# pi-crust15.net
KiCad netlist of a schematic drawn in EAGLE
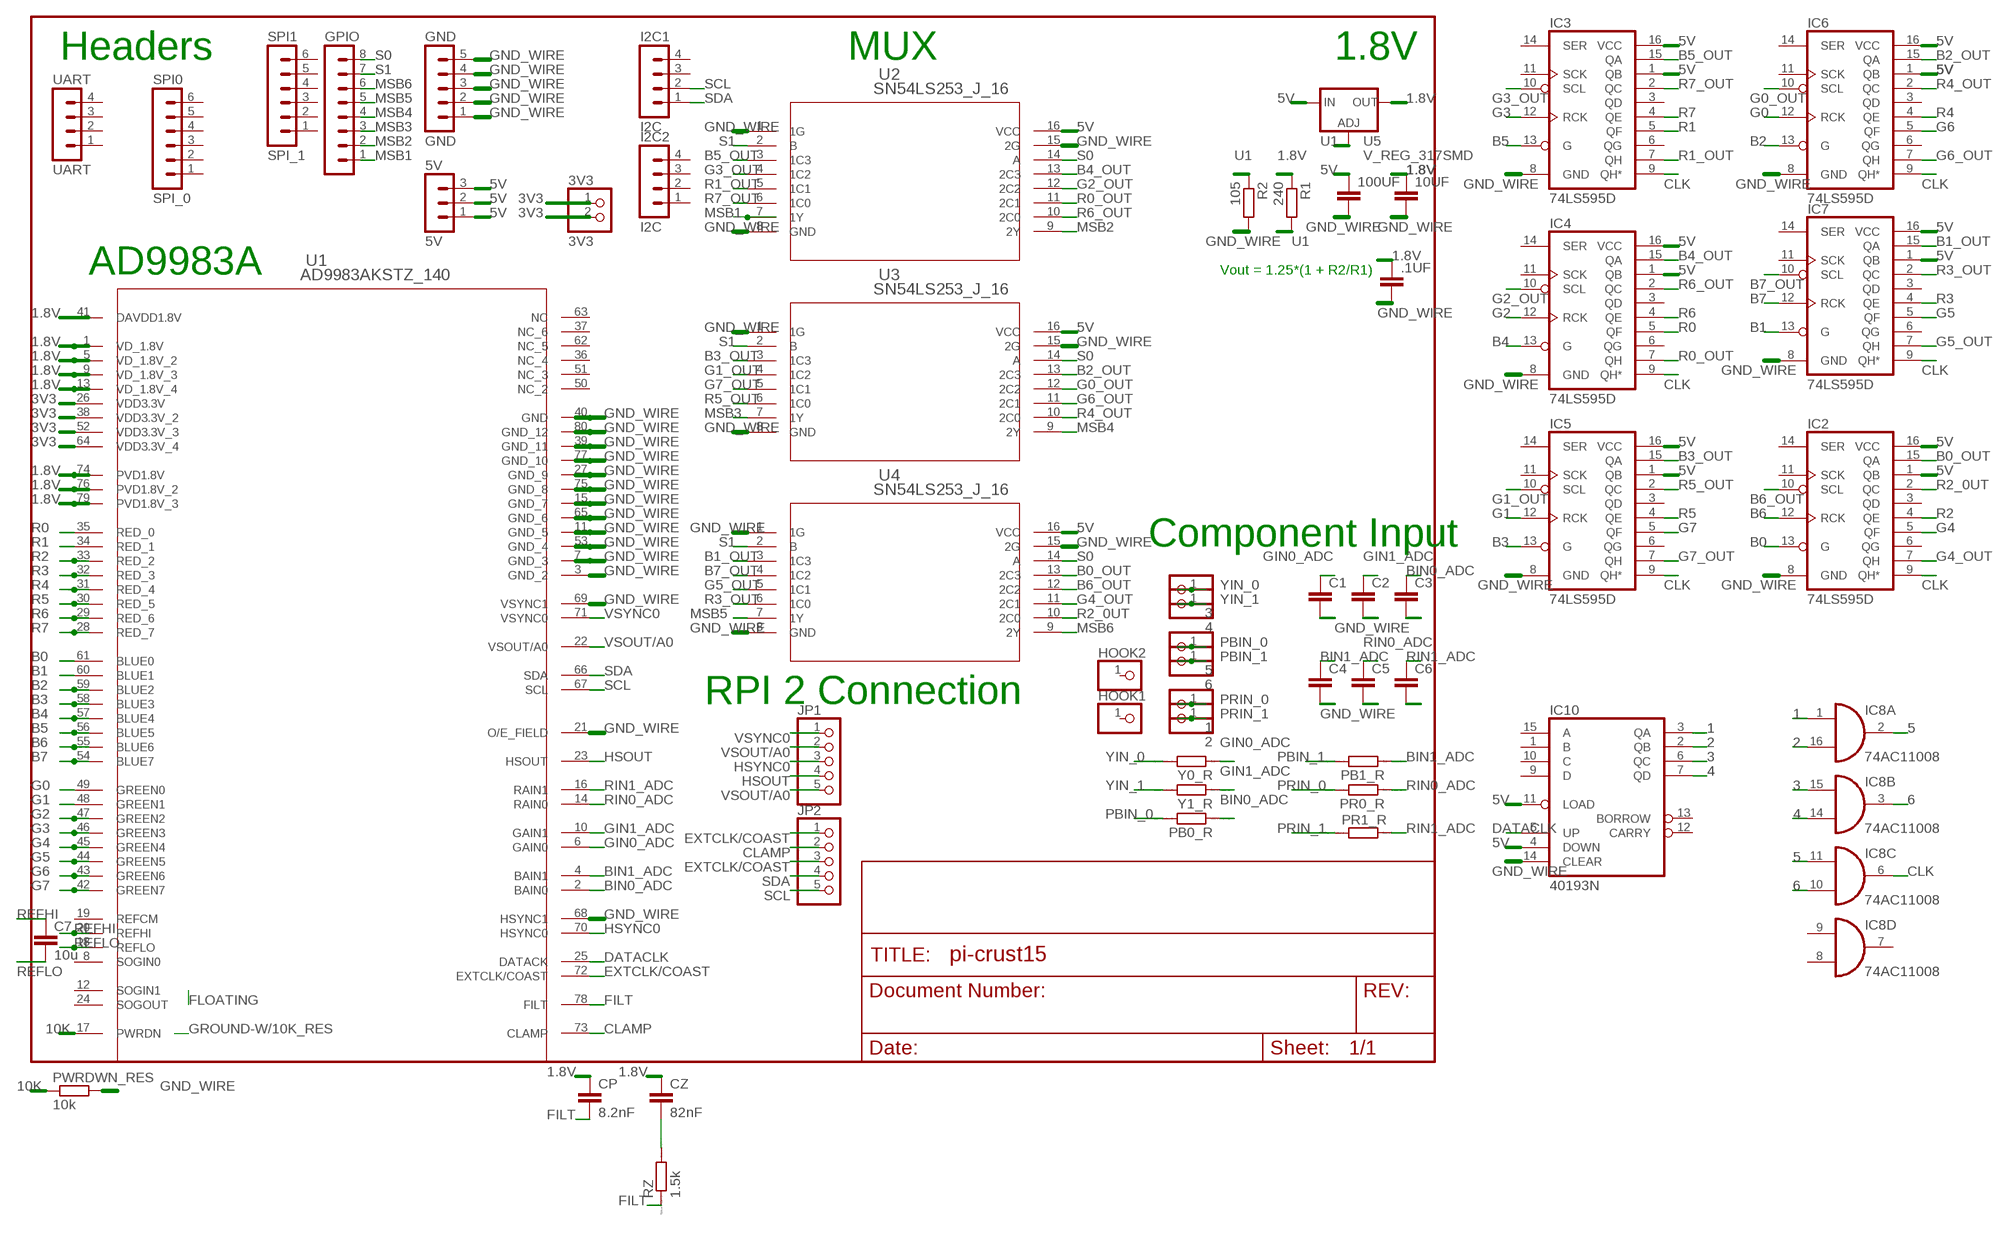
[diagram p0: schematic, sheet 1]

(export (version "E")
  (design (tool "Eeschema 10.0.6"))
  (components
    (comp (ref ".1UF")
      (value "C2.5/5")
      (footprint "eagle-import:C2.5-5")
      (libsource (lib "eagle-import") (part "C2.5/5"))
    )
    (comp (ref "1")
      (value "PINHD-1X1")
      (footprint "eagle-import:1X01")
      (libsource (lib "eagle-import") (part "PINHD-1X1"))
    )
    (comp (ref "2")
      (value "PINHD-1X1")
      (footprint "eagle-import:1X01")
      (libsource (lib "eagle-import") (part "PINHD-1X1"))
    )
    (comp (ref "3")
      (value "PINHD-1X1")
      (footprint "eagle-import:1X01")
      (libsource (lib "eagle-import") (part "PINHD-1X1"))
    )
    (comp (ref "3V3")
      (value "3V3")
      (footprint "eagle-import:1X02")
      (libsource (lib "eagle-import") (part "PINHD-1X2"))
    )
    (comp (ref "4")
      (value "PINHD-1X1")
      (footprint "eagle-import:1X01")
      (libsource (lib "eagle-import") (part "PINHD-1X1"))
    )
    (comp (ref "5")
      (value "PINHD-1X1")
      (footprint "eagle-import:1X01")
      (libsource (lib "eagle-import") (part "PINHD-1X1"))
    )
    (comp (ref "5V")
      (value "5V")
      (footprint "eagle-import:MA03-1")
      (libsource (lib "eagle-import") (part "MA03-1"))
    )
    (comp (ref "6")
      (value "PINHD-1X1")
      (footprint "eagle-import:1X01")
      (libsource (lib "eagle-import") (part "PINHD-1X1"))
    )
    (comp (ref "10UF")
      (value "C2.5/5")
      (footprint "eagle-import:C2.5-5")
      (libsource (lib "eagle-import") (part "C2.5/5"))
    )
    (comp (ref "100UF")
      (value "C2.5/5")
      (footprint "eagle-import:C2.5-5")
      (libsource (lib "eagle-import") (part "C2.5/5"))
    )
    (comp (ref "C1")
      (value "C2.5/5")
      (footprint "eagle-import:C2.5-5")
      (libsource (lib "eagle-import") (part "C2.5/5"))
    )
    (comp (ref "C2")
      (value "C2.5/5")
      (footprint "eagle-import:C2.5-5")
      (libsource (lib "eagle-import") (part "C2.5/5"))
    )
    (comp (ref "C3")
      (value "C2.5/5")
      (footprint "eagle-import:C2.5-5")
      (libsource (lib "eagle-import") (part "C2.5/5"))
    )
    (comp (ref "C4")
      (value "C2.5/5")
      (footprint "eagle-import:C2.5-5")
      (libsource (lib "eagle-import") (part "C2.5/5"))
    )
    (comp (ref "C5")
      (value "C2.5/5")
      (footprint "eagle-import:C2.5-5")
      (libsource (lib "eagle-import") (part "C2.5/5"))
    )
    (comp (ref "C6")
      (value "C2.5/5")
      (footprint "eagle-import:C2.5-5")
      (libsource (lib "eagle-import") (part "C2.5/5"))
    )
    (comp (ref "C7")
      (value "10u")
      (footprint "eagle-import:C2.5-5")
      (libsource (lib "eagle-import") (part "C2.5/5"))
    )
    (comp (ref "CP")
      (value "8.2nF")
      (footprint "eagle-import:C2.5-5")
      (libsource (lib "eagle-import") (part "C2.5/5"))
    )
    (comp (ref "CZ")
      (value "82nF")
      (footprint "eagle-import:C2.5-5")
      (libsource (lib "eagle-import") (part "C2.5/5"))
    )
    (comp (ref "GND")
      (value "GND")
      (footprint "eagle-import:MA05-1")
      (libsource (lib "eagle-import") (part "MA05-1"))
    )
    (comp (ref "GPIO")
      (value "MA08-1")
      (footprint "eagle-import:MA08-1")
      (libsource (lib "eagle-import") (part "MA08-1"))
    )
    (comp (ref "HOOK1")
      (value "PINHD-1X1")
      (footprint "eagle-import:1X01")
      (libsource (lib "eagle-import") (part "PINHD-1X1"))
    )
    (comp (ref "HOOK2")
      (value "PINHD-1X1")
      (footprint "eagle-import:1X01")
      (libsource (lib "eagle-import") (part "PINHD-1X1"))
    )
    (comp (ref "I2C1")
      (value "I2C")
      (footprint "eagle-import:MA04-1")
      (libsource (lib "eagle-import") (part "MA04-1"))
    )
    (comp (ref "I2C2")
      (value "I2C")
      (footprint "eagle-import:MA04-1")
      (libsource (lib "eagle-import") (part "MA04-1"))
    )
    (comp (ref "IC2")
      (value "74LS595D")
      (footprint "eagle-import:SO16")
      (libsource (lib "eagle-import") (part "74595DLS"))
    )
    (comp (ref "IC3")
      (value "74LS595D")
      (footprint "eagle-import:SO16")
      (libsource (lib "eagle-import") (part "74595DLS"))
    )
    (comp (ref "IC4")
      (value "74LS595D")
      (footprint "eagle-import:SO16")
      (libsource (lib "eagle-import") (part "74595DLS"))
    )
    (comp (ref "IC5")
      (value "74LS595D")
      (footprint "eagle-import:SO16")
      (libsource (lib "eagle-import") (part "74595DLS"))
    )
    (comp (ref "IC6")
      (value "74LS595D")
      (footprint "eagle-import:SO16")
      (libsource (lib "eagle-import") (part "74595DLS"))
    )
    (comp (ref "IC7")
      (value "74LS595D")
      (footprint "eagle-import:SO16")
      (libsource (lib "eagle-import") (part "74595DLS"))
    )
    (comp (ref "IC8")
      (value "74AC11008")
      (footprint "eagle-import:DIL16")
      (libsource (lib "eagle-import") (part "74AC11008"))
    )
    (comp (ref "IC10")
      (value "40193N")
      (footprint "eagle-import:DIL16")
      (libsource (lib "eagle-import") (part "40193N"))
    )
    (comp (ref "JP1")
      (value "PINHD-1X5")
      (footprint "eagle-import:1X05")
      (libsource (lib "eagle-import") (part "PINHD-1X5"))
    )
    (comp (ref "JP2")
      (value "PINHD-1X5")
      (footprint "eagle-import:1X05")
      (libsource (lib "eagle-import") (part "PINHD-1X5"))
    )
    (comp (ref "PB0_R")
      (value "R0204/7")
      (footprint "eagle-import:0204_7")
      (libsource (lib "eagle-import") (part "R0204/7"))
    )
    (comp (ref "PB1_R")
      (value "R0204/7")
      (footprint "eagle-import:0204_7")
      (libsource (lib "eagle-import") (part "R0204/7"))
    )
    (comp (ref "PR0_R")
      (value "R0204/7")
      (footprint "eagle-import:0204_7")
      (libsource (lib "eagle-import") (part "R0204/7"))
    )
    (comp (ref "PR1_R")
      (value "R0204/7")
      (footprint "eagle-import:0204_7")
      (libsource (lib "eagle-import") (part "R0204/7"))
    )
    (comp (ref "PWRDWN_RES")
      (value "10k")
      (footprint "eagle-import:0204_7")
      (libsource (lib "eagle-import") (part "R-EU_0204/7"))
    )
    (comp (ref "R1")
      (value "240")
      (footprint "eagle-import:0204_7")
      (libsource (lib "eagle-import") (part "R-EU_0204/7"))
    )
    (comp (ref "R2")
      (value "105")
      (footprint "eagle-import:0204_7")
      (libsource (lib "eagle-import") (part "R-EU_0204/7"))
    )
    (comp (ref "RZ")
      (value "1.5k")
      (footprint "eagle-import:0204_7")
      (libsource (lib "eagle-import") (part "R0204/7"))
    )
    (comp (ref "SPI0")
      (value "SPI_0")
      (footprint "eagle-import:MA06-1")
      (libsource (lib "eagle-import") (part "MA06-1"))
    )
    (comp (ref "SPI1")
      (value "SPI_1")
      (footprint "eagle-import:MA06-1")
      (libsource (lib "eagle-import") (part "MA06-1"))
    )
    (comp (ref "U1")
      (value "AD9983AKSTZ_140")
      (footprint "eagle-import:ST_80_2")
      (libsource (lib "eagle-import") (part "AD9983AKSTZ_140"))
    )
    (comp (ref "U2")
      (value "SN54LS253_J_16")
      (footprint "eagle-import:J16")
      (fields
        (field (name "GENERIC_PART_NUMBER") "SN54LS253")
        (field (name "MANUFACTURER") "Texas Instruments")
      )
      (libsource (lib "eagle-import") (part "SN54LS253_J_16"))
    )
    (comp (ref "U3")
      (value "SN54LS253_J_16")
      (footprint "eagle-import:J16")
      (fields
        (field (name "GENERIC_PART_NUMBER") "SN54LS253")
        (field (name "MANUFACTURER") "Texas Instruments")
      )
      (libsource (lib "eagle-import") (part "SN54LS253_J_16"))
    )
    (comp (ref "U4")
      (value "SN54LS253_J_16")
      (footprint "eagle-import:J16")
      (fields
        (field (name "GENERIC_PART_NUMBER") "SN54LS253")
        (field (name "MANUFACTURER") "Texas Instruments")
      )
      (libsource (lib "eagle-import") (part "SN54LS253_J_16"))
    )
    (comp (ref "U5")
      (value "V_REG_317SMD")
      (footprint "eagle-import:SOT223")
      (libsource (lib "eagle-import") (part "V_REG_317SMD"))
    )
    (comp (ref "UART")
      (value "UART")
      (footprint "eagle-import:MA04-1")
      (libsource (lib "eagle-import") (part "MA04-1"))
    )
    (comp (ref "Y0_R")
      (value "R0204/7")
      (footprint "eagle-import:0204_7")
      (libsource (lib "eagle-import") (part "R0204/7"))
    )
    (comp (ref "Y1_R")
      (value "R0204/7")
      (footprint "eagle-import:0204_7")
      (libsource (lib "eagle-import") (part "R0204/7"))
    )
  )
  (nets
    (net (code "1") (name "/1") (class "Default")
      (node (ref "IC10") (pin "3") (pinfunction "QA_3") (pintype "output"))
      (node (ref "IC8") (pin "1") (pinfunction "I0_1") (pintype "input"))
    )
    (net (code "2") (name "/1.8V") (class "Default")
      (node (ref ".1UF") (pin "1") (pinfunction "1_1") (pintype "passive"))
      (node (ref "10UF") (pin "1") (pinfunction "1_1") (pintype "passive"))
      (node (ref "CP") (pin "1") (pinfunction "1_1") (pintype "passive"))
      (node (ref "CZ") (pin "1") (pinfunction "1_1") (pintype "passive"))
      (node (ref "R1") (pin "1") (pinfunction "1_1") (pintype "passive"))
      (node (ref "U1") (pin "1") (pinfunction "VD_1.8V_1") (pintype "passive"))
      (node (ref "U1") (pin "13") (pinfunction "VD_1.8V_4_13") (pintype "passive"))
      (node (ref "U1") (pin "41") (pinfunction "DAVDD1.8V_41") (pintype "passive"))
      (node (ref "U1") (pin "5") (pinfunction "VD_1.8V_2_5") (pintype "passive"))
      (node (ref "U1") (pin "74") (pinfunction "PVD1.8V_74") (pintype "passive"))
      (node (ref "U1") (pin "76") (pinfunction "PVD1.8V_2_76") (pintype "passive"))
      (node (ref "U1") (pin "79") (pinfunction "PVD1.8V_3_79") (pintype "passive"))
      (node (ref "U1") (pin "9") (pinfunction "VD_1.8V_3_9") (pintype "passive"))
      (node (ref "U5") (pin "2") (pinfunction "OUT_2") (pintype "output"))
    )
    (net (code "3") (name "/2") (class "Default")
      (node (ref "IC10") (pin "2") (pinfunction "QB_2") (pintype "output"))
      (node (ref "IC8") (pin "16") (pinfunction "I1_16") (pintype "input"))
    )
    (net (code "4") (name "/3") (class "Default")
      (node (ref "IC10") (pin "6") (pinfunction "QC_6") (pintype "output"))
      (node (ref "IC8") (pin "15") (pinfunction "I0_15") (pintype "input"))
    )
    (net (code "5") (name "/3V3") (class "Default")
      (node (ref "3V3") (pin "1") (pinfunction "1_1") (pintype "passive"))
      (node (ref "3V3") (pin "2") (pinfunction "2_2") (pintype "passive"))
      (node (ref "U1") (pin "26") (pinfunction "VDD3.3V_26") (pintype "passive"))
      (node (ref "U1") (pin "38") (pinfunction "VDD3.3V_2_38") (pintype "passive"))
      (node (ref "U1") (pin "52") (pinfunction "VDD3.3V_3_52") (pintype "passive"))
      (node (ref "U1") (pin "64") (pinfunction "VDD3.3V_4_64") (pintype "passive"))
    )
    (net (code "6") (name "/4") (class "Default")
      (node (ref "IC10") (pin "7") (pinfunction "QD_7") (pintype "output"))
      (node (ref "IC8") (pin "14") (pinfunction "I1_14") (pintype "input"))
    )
    (net (code "7") (name "/5") (class "Default")
      (node (ref "IC8") (pin "11") (pinfunction "I0_11") (pintype "input"))
      (node (ref "IC8") (pin "2") (pinfunction "O_2") (pintype "output"))
    )
    (net (code "8") (name "/5V") (class "Default")
      (node (ref "100UF") (pin "1") (pinfunction "1_1") (pintype "passive"))
      (node (ref "5V") (pin "1") (pinfunction "1_1") (pintype "passive"))
      (node (ref "5V") (pin "2") (pinfunction "2_2") (pintype "passive"))
      (node (ref "5V") (pin "3") (pinfunction "3_3") (pintype "passive"))
      (node (ref "IC10") (pin "11") (pinfunction "LOAD_11") (pintype "input"))
      (node (ref "IC10") (pin "4") (pinfunction "DOWN_4") (pintype "input"))
      (node (ref "IC2") (pin "1") (pinfunction "QB_1") (pintype "tri_state"))
      (node (ref "IC2") (pin "16") (pinfunction "VCC_16") (pintype "power_in"))
      (node (ref "IC3") (pin "1") (pinfunction "QB_1") (pintype "tri_state"))
      (node (ref "IC3") (pin "16") (pinfunction "VCC_16") (pintype "power_in"))
      (node (ref "IC4") (pin "1") (pinfunction "QB_1") (pintype "tri_state"))
      (node (ref "IC4") (pin "16") (pinfunction "VCC_16") (pintype "power_in"))
      (node (ref "IC5") (pin "1") (pinfunction "QB_1") (pintype "tri_state"))
      (node (ref "IC5") (pin "16") (pinfunction "VCC_16") (pintype "power_in"))
      (node (ref "IC6") (pin "1") (pinfunction "QB_1") (pintype "tri_state"))
      (node (ref "IC6") (pin "16") (pinfunction "VCC_16") (pintype "power_in"))
      (node (ref "IC7") (pin "1") (pinfunction "QB_1") (pintype "tri_state"))
      (node (ref "IC7") (pin "16") (pinfunction "VCC_16") (pintype "power_in"))
      (node (ref "U2") (pin "16") (pinfunction "VCC_16") (pintype "power_in"))
      (node (ref "U3") (pin "16") (pinfunction "VCC_16") (pintype "power_in"))
      (node (ref "U4") (pin "16") (pinfunction "VCC_16") (pintype "power_in"))
      (node (ref "U5") (pin "3") (pinfunction "IN_3") (pintype "input"))
    )
    (net (code "9") (name "/6") (class "Default")
      (node (ref "IC8") (pin "10") (pinfunction "I1_10") (pintype "input"))
      (node (ref "IC8") (pin "3") (pinfunction "O_3") (pintype "output"))
    )
    (net (code "10") (name "/10K") (class "Default")
      (node (ref "PWRDWN_RES") (pin "1") (pinfunction "1_1") (pintype "passive"))
      (node (ref "U1") (pin "17") (pinfunction "PWRDN_17") (pintype "passive"))
    )
    (net (code "11") (name "/B0") (class "Default")
      (node (ref "IC2") (pin "13") (pinfunction "G_13") (pintype "input"))
      (node (ref "U1") (pin "61") (pinfunction "BLUE0_61") (pintype "passive"))
    )
    (net (code "12") (name "/B0_OUT") (class "Default")
      (node (ref "IC2") (pin "15") (pinfunction "QA_15") (pintype "tri_state"))
      (node (ref "U4") (pin "13") (pinfunction "2C3_13") (pintype "input"))
    )
    (net (code "13") (name "/B1") (class "Default")
      (node (ref "IC7") (pin "13") (pinfunction "G_13") (pintype "input"))
      (node (ref "U1") (pin "60") (pinfunction "BLUE1_60") (pintype "passive"))
    )
    (net (code "14") (name "/B1_OUT") (class "Default")
      (node (ref "IC7") (pin "15") (pinfunction "QA_15") (pintype "tri_state"))
      (node (ref "U4") (pin "3") (pinfunction "1C3_3") (pintype "input"))
    )
    (net (code "15") (name "/B2") (class "Default")
      (node (ref "IC6") (pin "13") (pinfunction "G_13") (pintype "input"))
      (node (ref "U1") (pin "59") (pinfunction "BLUE2_59") (pintype "passive"))
    )
    (net (code "16") (name "/B2_OUT") (class "Default")
      (node (ref "IC6") (pin "15") (pinfunction "QA_15") (pintype "tri_state"))
      (node (ref "U3") (pin "13") (pinfunction "2C3_13") (pintype "input"))
    )
    (net (code "17") (name "/B3") (class "Default")
      (node (ref "IC5") (pin "13") (pinfunction "G_13") (pintype "input"))
      (node (ref "U1") (pin "58") (pinfunction "BLUE3_58") (pintype "passive"))
    )
    (net (code "18") (name "/B3_OUT") (class "Default")
      (node (ref "IC5") (pin "15") (pinfunction "QA_15") (pintype "tri_state"))
      (node (ref "U3") (pin "3") (pinfunction "1C3_3") (pintype "input"))
    )
    (net (code "19") (name "/B4") (class "Default")
      (node (ref "IC4") (pin "13") (pinfunction "G_13") (pintype "input"))
      (node (ref "U1") (pin "57") (pinfunction "BLUE4_57") (pintype "passive"))
    )
    (net (code "20") (name "/B4_OUT") (class "Default")
      (node (ref "IC4") (pin "15") (pinfunction "QA_15") (pintype "tri_state"))
      (node (ref "U2") (pin "13") (pinfunction "2C3_13") (pintype "input"))
    )
    (net (code "21") (name "/B5") (class "Default")
      (node (ref "IC3") (pin "13") (pinfunction "G_13") (pintype "input"))
      (node (ref "U1") (pin "56") (pinfunction "BLUE5_56") (pintype "passive"))
    )
    (net (code "22") (name "/B5_OUT") (class "Default")
      (node (ref "IC3") (pin "15") (pinfunction "QA_15") (pintype "tri_state"))
      (node (ref "U2") (pin "3") (pinfunction "1C3_3") (pintype "input"))
    )
    (net (code "23") (name "/B6") (class "Default")
      (node (ref "IC2") (pin "12") (pinfunction "RCK_12") (pintype "input"))
      (node (ref "U1") (pin "55") (pinfunction "BLUE6_55") (pintype "passive"))
    )
    (net (code "24") (name "/B6_OUT") (class "Default")
      (node (ref "IC2") (pin "10") (pinfunction "SCL_10") (pintype "input"))
      (node (ref "U4") (pin "12") (pinfunction "2C2_12") (pintype "input"))
    )
    (net (code "25") (name "/B7") (class "Default")
      (node (ref "IC7") (pin "12") (pinfunction "RCK_12") (pintype "input"))
      (node (ref "U1") (pin "54") (pinfunction "BLUE7_54") (pintype "passive"))
    )
    (net (code "26") (name "/B7_OUT") (class "Default")
      (node (ref "IC7") (pin "10") (pinfunction "SCL_10") (pintype "input"))
      (node (ref "U4") (pin "4") (pinfunction "1C2_4") (pintype "input"))
    )
    (net (code "27") (name "/BIN0_ADC") (class "Default")
      (node (ref "C3") (pin "1") (pinfunction "1_1") (pintype "passive"))
      (node (ref "PB0_R") (pin "1") (pinfunction "1_1") (pintype "passive"))
      (node (ref "U1") (pin "2") (pinfunction "BAIN0_2") (pintype "passive"))
    )
    (net (code "28") (name "/BIN1_ADC") (class "Default")
      (node (ref "C4") (pin "1") (pinfunction "1_1") (pintype "passive"))
      (node (ref "PB1_R") (pin "1") (pinfunction "1_1") (pintype "passive"))
      (node (ref "U1") (pin "4") (pinfunction "BAIN1_4") (pintype "passive"))
    )
    (net (code "29") (name "/CLAMP") (class "Default")
      (node (ref "JP2") (pin "2") (pinfunction "2_2") (pintype "passive"))
      (node (ref "U1") (pin "73") (pinfunction "CLAMP_73") (pintype "passive"))
    )
    (net (code "30") (name "/CLK") (class "Default")
      (node (ref "IC2") (pin "9") (pinfunction "QH*_9") (pintype "tri_state"))
      (node (ref "IC3") (pin "9") (pinfunction "QH*_9") (pintype "tri_state"))
      (node (ref "IC4") (pin "9") (pinfunction "QH*_9") (pintype "tri_state"))
      (node (ref "IC5") (pin "9") (pinfunction "QH*_9") (pintype "tri_state"))
      (node (ref "IC6") (pin "9") (pinfunction "QH*_9") (pintype "tri_state"))
      (node (ref "IC7") (pin "9") (pinfunction "QH*_9") (pintype "tri_state"))
      (node (ref "IC8") (pin "6") (pinfunction "O_6") (pintype "output"))
    )
    (net (code "31") (name "/DATACLK") (class "Default")
      (node (ref "IC10") (pin "5") (pinfunction "UP_5") (pintype "input"))
      (node (ref "U1") (pin "25") (pinfunction "DATACK_25") (pintype "passive"))
    )
    (net (code "32") (name "/EXTCLK{slash}COAST") (class "Default")
      (node (ref "JP2") (pin "1") (pinfunction "1_1") (pintype "passive"))
      (node (ref "JP2") (pin "3") (pinfunction "3_3") (pintype "passive"))
      (node (ref "U1") (pin "72") (pinfunction "EXTCLK/COAST_72") (pintype "passive"))
    )
    (net (code "33") (name "/FILT") (class "Default")
      (node (ref "CP") (pin "2") (pinfunction "2_2") (pintype "passive"))
      (node (ref "RZ") (pin "1") (pinfunction "1_1") (pintype "passive"))
      (node (ref "U1") (pin "78") (pinfunction "FILT_78") (pintype "passive"))
    )
    (net (code "35") (name "/G0") (class "Default")
      (node (ref "IC6") (pin "12") (pinfunction "RCK_12") (pintype "input"))
      (node (ref "U1") (pin "49") (pinfunction "GREEN0_49") (pintype "passive"))
    )
    (net (code "36") (name "/G0_OUT") (class "Default")
      (node (ref "IC6") (pin "10") (pinfunction "SCL_10") (pintype "input"))
      (node (ref "U3") (pin "12") (pinfunction "2C2_12") (pintype "input"))
    )
    (net (code "37") (name "/G1") (class "Default")
      (node (ref "IC5") (pin "12") (pinfunction "RCK_12") (pintype "input"))
      (node (ref "U1") (pin "48") (pinfunction "GREEN1_48") (pintype "passive"))
    )
    (net (code "38") (name "/G1_OUT") (class "Default")
      (node (ref "IC5") (pin "10") (pinfunction "SCL_10") (pintype "input"))
      (node (ref "U3") (pin "4") (pinfunction "1C2_4") (pintype "input"))
    )
    (net (code "39") (name "/G2") (class "Default")
      (node (ref "IC4") (pin "12") (pinfunction "RCK_12") (pintype "input"))
      (node (ref "U1") (pin "47") (pinfunction "GREEN2_47") (pintype "passive"))
    )
    (net (code "40") (name "/G2_OUT") (class "Default")
      (node (ref "IC4") (pin "10") (pinfunction "SCL_10") (pintype "input"))
      (node (ref "U2") (pin "12") (pinfunction "2C2_12") (pintype "input"))
    )
    (net (code "41") (name "/G3") (class "Default")
      (node (ref "IC3") (pin "12") (pinfunction "RCK_12") (pintype "input"))
      (node (ref "U1") (pin "46") (pinfunction "GREEN3_46") (pintype "passive"))
    )
    (net (code "42") (name "/G3_OUT") (class "Default")
      (node (ref "IC3") (pin "10") (pinfunction "SCL_10") (pintype "input"))
      (node (ref "U2") (pin "4") (pinfunction "1C2_4") (pintype "input"))
    )
    (net (code "43") (name "/G4") (class "Default")
      (node (ref "IC2") (pin "5") (pinfunction "QF_5") (pintype "tri_state"))
      (node (ref "U1") (pin "45") (pinfunction "GREEN4_45") (pintype "passive"))
    )
    (net (code "44") (name "/G4_OUT") (class "Default")
      (node (ref "IC2") (pin "7") (pinfunction "QH_7") (pintype "tri_state"))
      (node (ref "U4") (pin "11") (pinfunction "2C1_11") (pintype "input"))
    )
    (net (code "45") (name "/G5") (class "Default")
      (node (ref "IC7") (pin "5") (pinfunction "QF_5") (pintype "tri_state"))
      (node (ref "U1") (pin "44") (pinfunction "GREEN5_44") (pintype "passive"))
    )
    (net (code "46") (name "/G5_OUT") (class "Default")
      (node (ref "IC7") (pin "7") (pinfunction "QH_7") (pintype "tri_state"))
      (node (ref "U4") (pin "5") (pinfunction "1C1_5") (pintype "input"))
    )
    (net (code "47") (name "/G6") (class "Default")
      (node (ref "IC6") (pin "5") (pinfunction "QF_5") (pintype "tri_state"))
      (node (ref "U1") (pin "43") (pinfunction "GREEN6_43") (pintype "passive"))
    )
    (net (code "48") (name "/G6_OUT") (class "Default")
      (node (ref "IC6") (pin "7") (pinfunction "QH_7") (pintype "tri_state"))
      (node (ref "U3") (pin "11") (pinfunction "2C1_11") (pintype "input"))
    )
    (net (code "49") (name "/G7") (class "Default")
      (node (ref "IC5") (pin "5") (pinfunction "QF_5") (pintype "tri_state"))
      (node (ref "U1") (pin "42") (pinfunction "GREEN7_42") (pintype "passive"))
    )
    (net (code "50") (name "/G7_OUT") (class "Default")
      (node (ref "IC5") (pin "7") (pinfunction "QH_7") (pintype "tri_state"))
      (node (ref "U3") (pin "5") (pinfunction "1C1_5") (pintype "input"))
    )
    (net (code "51") (name "/GIN0_ADC") (class "Default")
      (node (ref "C1") (pin "1") (pinfunction "1_1") (pintype "passive"))
      (node (ref "U1") (pin "6") (pinfunction "GAIN0_6") (pintype "passive"))
      (node (ref "Y0_R") (pin "1") (pinfunction "1_1") (pintype "passive"))
    )
    (net (code "52") (name "/GIN1_ADC") (class "Default")
      (node (ref "C2") (pin "1") (pinfunction "1_1") (pintype "passive"))
      (node (ref "U1") (pin "10") (pinfunction "GAIN1_10") (pintype "passive"))
      (node (ref "Y1_R") (pin "1") (pinfunction "1_1") (pintype "passive"))
    )
    (net (code "53") (name "/GND_WIRE") (class "Default")
      (node (ref ".1UF") (pin "2") (pinfunction "2_2") (pintype "passive"))
      (node (ref "100UF") (pin "2") (pinfunction "2_2") (pintype "passive"))
      (node (ref "10UF") (pin "2") (pinfunction "2_2") (pintype "passive"))
      (node (ref "C1") (pin "2") (pinfunction "2_2") (pintype "passive"))
      (node (ref "C2") (pin "2") (pinfunction "2_2") (pintype "passive"))
      (node (ref "C3") (pin "2") (pinfunction "2_2") (pintype "passive"))
      (node (ref "C4") (pin "2") (pinfunction "2_2") (pintype "passive"))
      (node (ref "C5") (pin "2") (pinfunction "2_2") (pintype "passive"))
      (node (ref "C6") (pin "2") (pinfunction "2_2") (pintype "passive"))
      (node (ref "GND") (pin "1") (pinfunction "1_1") (pintype "passive"))
      (node (ref "GND") (pin "2") (pinfunction "2_2") (pintype "passive"))
      (node (ref "GND") (pin "3") (pinfunction "3_3") (pintype "passive"))
      (node (ref "GND") (pin "4") (pinfunction "4_4") (pintype "passive"))
      (node (ref "GND") (pin "5") (pinfunction "5_5") (pintype "passive"))
      (node (ref "IC10") (pin "14") (pinfunction "CLEAR_14") (pintype "input"))
      (node (ref "IC2") (pin "8") (pinfunction "GND_8") (pintype "power_in"))
      (node (ref "IC3") (pin "8") (pinfunction "GND_8") (pintype "power_in"))
      (node (ref "IC4") (pin "8") (pinfunction "GND_8") (pintype "power_in"))
      (node (ref "IC5") (pin "8") (pinfunction "GND_8") (pintype "power_in"))
      (node (ref "IC6") (pin "8") (pinfunction "GND_8") (pintype "power_in"))
      (node (ref "IC7") (pin "8") (pinfunction "GND_8") (pintype "power_in"))
      (node (ref "PWRDWN_RES") (pin "2") (pinfunction "2_2") (pintype "passive"))
      (node (ref "R2") (pin "2") (pinfunction "2_2") (pintype "passive"))
      (node (ref "U1") (pin "11") (pinfunction "GND_5_11") (pintype "passive"))
      (node (ref "U1") (pin "15") (pinfunction "GND_7_15") (pintype "passive"))
      (node (ref "U1") (pin "21") (pinfunction "O/E_FIELD_21") (pintype "passive"))
      (node (ref "U1") (pin "27") (pinfunction "GND_9_27") (pintype "passive"))
      (node (ref "U1") (pin "3") (pinfunction "GND_2_3") (pintype "passive"))
      (node (ref "U1") (pin "39") (pinfunction "GND_11_39") (pintype "passive"))
      (node (ref "U1") (pin "40") (pinfunction "GND_40") (pintype "passive"))
      (node (ref "U1") (pin "53") (pinfunction "GND_4_53") (pintype "passive"))
      (node (ref "U1") (pin "65") (pinfunction "GND_6_65") (pintype "passive"))
      (node (ref "U1") (pin "68") (pinfunction "HSYNC1_68") (pintype "passive"))
      (node (ref "U1") (pin "69") (pinfunction "VSYNC1_69") (pintype "passive"))
      (node (ref "U1") (pin "7") (pinfunction "GND_3_7") (pintype "passive"))
      (node (ref "U1") (pin "75") (pinfunction "GND_8_75") (pintype "passive"))
      (node (ref "U1") (pin "77") (pinfunction "GND_10_77") (pintype "passive"))
      (node (ref "U1") (pin "80") (pinfunction "GND_12_80") (pintype "passive"))
      (node (ref "U2") (pin "1") (pinfunction "1G_1") (pintype "input"))
      (node (ref "U2") (pin "15") (pinfunction "2G_15") (pintype "input"))
      (node (ref "U2") (pin "8") (pinfunction "GND_8") (pintype "power_in"))
      (node (ref "U3") (pin "1") (pinfunction "1G_1") (pintype "input"))
      (node (ref "U3") (pin "15") (pinfunction "2G_15") (pintype "input"))
      (node (ref "U3") (pin "8") (pinfunction "GND_8") (pintype "power_in"))
      (node (ref "U4") (pin "1") (pinfunction "1G_1") (pintype "input"))
      (node (ref "U4") (pin "15") (pinfunction "2G_15") (pintype "input"))
      (node (ref "U4") (pin "8") (pinfunction "GND_8") (pintype "power_in"))
    )
    (net (code "55") (name "/HSOUT") (class "Default")
      (node (ref "JP1") (pin "4") (pinfunction "4_4") (pintype "passive"))
      (node (ref "U1") (pin "23") (pinfunction "HSOUT_23") (pintype "passive"))
    )
    (net (code "56") (name "/HSYNC0") (class "Default")
      (node (ref "JP1") (pin "3") (pinfunction "3_3") (pintype "passive"))
      (node (ref "U1") (pin "70") (pinfunction "HSYNC0_70") (pintype "passive"))
    )
    (net (code "57") (name "/MSB1") (class "Default")
      (node (ref "GPIO") (pin "1") (pinfunction "1_1") (pintype "passive"))
      (node (ref "U2") (pin "7") (pinfunction "1Y_7") (pintype "output"))
    )
    (net (code "58") (name "/MSB2") (class "Default")
      (node (ref "GPIO") (pin "2") (pinfunction "2_2") (pintype "passive"))
      (node (ref "U2") (pin "9") (pinfunction "2Y_9") (pintype "output"))
    )
    (net (code "59") (name "/MSB3") (class "Default")
      (node (ref "GPIO") (pin "3") (pinfunction "3_3") (pintype "passive"))
      (node (ref "U3") (pin "7") (pinfunction "1Y_7") (pintype "output"))
    )
    (net (code "60") (name "/MSB4") (class "Default")
      (node (ref "GPIO") (pin "4") (pinfunction "4_4") (pintype "passive"))
      (node (ref "U3") (pin "9") (pinfunction "2Y_9") (pintype "output"))
    )
    (net (code "61") (name "/MSB5") (class "Default")
      (node (ref "GPIO") (pin "5") (pinfunction "5_5") (pintype "passive"))
      (node (ref "U4") (pin "7") (pinfunction "1Y_7") (pintype "output"))
    )
    (net (code "62") (name "/MSB6") (class "Default")
      (node (ref "GPIO") (pin "6") (pinfunction "6_6") (pintype "passive"))
      (node (ref "U4") (pin "9") (pinfunction "2Y_9") (pintype "output"))
    )
    (net (code "63") (name "/PBIN_0") (class "Default")
      (node (ref "5") (pin "1") (pinfunction "1_1") (pintype "passive"))
      (node (ref "PB0_R") (pin "2") (pinfunction "2_2") (pintype "passive"))
    )
    (net (code "64") (name "/PBIN_1") (class "Default")
      (node (ref "6") (pin "1") (pinfunction "1_1") (pintype "passive"))
      (node (ref "PB1_R") (pin "2") (pinfunction "2_2") (pintype "passive"))
    )
    (net (code "65") (name "/PRIN_0") (class "Default")
      (node (ref "1") (pin "1") (pinfunction "1_1") (pintype "passive"))
      (node (ref "PR0_R") (pin "2") (pinfunction "2_2") (pintype "passive"))
    )
    (net (code "66") (name "/PRIN_1") (class "Default")
      (node (ref "2") (pin "1") (pinfunction "1_1") (pintype "passive"))
      (node (ref "PR1_R") (pin "1") (pinfunction "1_1") (pintype "passive"))
    )
    (net (code "67") (name "/R0") (class "Default")
      (node (ref "IC4") (pin "5") (pinfunction "QF_5") (pintype "tri_state"))
      (node (ref "U1") (pin "35") (pinfunction "RED_0_35") (pintype "passive"))
    )
    (net (code "68") (name "/R0_OUT") (class "Default")
      (node (ref "IC4") (pin "7") (pinfunction "QH_7") (pintype "tri_state"))
      (node (ref "U2") (pin "11") (pinfunction "2C1_11") (pintype "input"))
    )
    (net (code "69") (name "/R1") (class "Default")
      (node (ref "IC3") (pin "5") (pinfunction "QF_5") (pintype "tri_state"))
      (node (ref "U1") (pin "34") (pinfunction "RED_1_34") (pintype "passive"))
    )
    (net (code "70") (name "/R1_OUT") (class "Default")
      (node (ref "IC3") (pin "7") (pinfunction "QH_7") (pintype "tri_state"))
      (node (ref "U2") (pin "5") (pinfunction "1C1_5") (pintype "input"))
    )
    (net (code "71") (name "/R2") (class "Default")
      (node (ref "IC2") (pin "4") (pinfunction "QE_4") (pintype "tri_state"))
      (node (ref "U1") (pin "33") (pinfunction "RED_2_33") (pintype "passive"))
    )
    (net (code "72") (name "/R2_0UT") (class "Default")
      (node (ref "IC2") (pin "2") (pinfunction "QC_2") (pintype "tri_state"))
      (node (ref "U4") (pin "10") (pinfunction "2C0_10") (pintype "input"))
    )
    (net (code "73") (name "/R3") (class "Default")
      (node (ref "IC7") (pin "4") (pinfunction "QE_4") (pintype "tri_state"))
      (node (ref "U1") (pin "32") (pinfunction "RED_3_32") (pintype "passive"))
    )
    (net (code "74") (name "/R3_OUT") (class "Default")
      (node (ref "IC7") (pin "2") (pinfunction "QC_2") (pintype "tri_state"))
      (node (ref "U4") (pin "6") (pinfunction "1C0_6") (pintype "input"))
    )
    (net (code "75") (name "/R4") (class "Default")
      (node (ref "IC6") (pin "4") (pinfunction "QE_4") (pintype "tri_state"))
      (node (ref "U1") (pin "31") (pinfunction "RED_4_31") (pintype "passive"))
    )
    (net (code "76") (name "/R4_OUT") (class "Default")
      (node (ref "IC6") (pin "2") (pinfunction "QC_2") (pintype "tri_state"))
      (node (ref "U3") (pin "10") (pinfunction "2C0_10") (pintype "input"))
    )
    (net (code "77") (name "/R5") (class "Default")
      (node (ref "IC5") (pin "4") (pinfunction "QE_4") (pintype "tri_state"))
      (node (ref "U1") (pin "30") (pinfunction "RED_5_30") (pintype "passive"))
    )
    (net (code "78") (name "/R5_OUT") (class "Default")
      (node (ref "IC5") (pin "2") (pinfunction "QC_2") (pintype "tri_state"))
      (node (ref "U3") (pin "6") (pinfunction "1C0_6") (pintype "input"))
    )
    (net (code "79") (name "/R6") (class "Default")
      (node (ref "IC4") (pin "4") (pinfunction "QE_4") (pintype "tri_state"))
      (node (ref "U1") (pin "29") (pinfunction "RED_6_29") (pintype "passive"))
    )
    (net (code "80") (name "/R6_OUT") (class "Default")
      (node (ref "IC4") (pin "2") (pinfunction "QC_2") (pintype "tri_state"))
      (node (ref "U2") (pin "10") (pinfunction "2C0_10") (pintype "input"))
    )
    (net (code "81") (name "/R7") (class "Default")
      (node (ref "IC3") (pin "4") (pinfunction "QE_4") (pintype "tri_state"))
      (node (ref "U1") (pin "28") (pinfunction "RED_7_28") (pintype "passive"))
    )
    (net (code "82") (name "/R7_OUT") (class "Default")
      (node (ref "IC3") (pin "2") (pinfunction "QC_2") (pintype "tri_state"))
      (node (ref "U2") (pin "6") (pinfunction "1C0_6") (pintype "input"))
    )
    (net (code "83") (name "/REFHI") (class "Default")
      (node (ref "C7") (pin "1") (pinfunction "1_1") (pintype "passive"))
      (node (ref "U1") (pin "20") (pinfunction "REFHI_20") (pintype "passive"))
    )
    (net (code "84") (name "/REFLO") (class "Default")
      (node (ref "C7") (pin "2") (pinfunction "2_2") (pintype "passive"))
      (node (ref "U1") (pin "18") (pinfunction "REFLO_18") (pintype "passive"))
    )
    (net (code "85") (name "/RIN0_ADC") (class "Default")
      (node (ref "C5") (pin "1") (pinfunction "1_1") (pintype "passive"))
      (node (ref "PR0_R") (pin "1") (pinfunction "1_1") (pintype "passive"))
      (node (ref "U1") (pin "14") (pinfunction "RAIN0_14") (pintype "passive"))
    )
    (net (code "86") (name "/RIN1_ADC") (class "Default")
      (node (ref "C6") (pin "1") (pinfunction "1_1") (pintype "passive"))
      (node (ref "PR1_R") (pin "2") (pinfunction "2_2") (pintype "passive"))
      (node (ref "U1") (pin "16") (pinfunction "RAIN1_16") (pintype "passive"))
    )
    (net (code "87") (name "/S0") (class "Default")
      (node (ref "GPIO") (pin "8") (pinfunction "8_8") (pintype "passive"))
      (node (ref "U2") (pin "14") (pinfunction "A_14") (pintype "input"))
      (node (ref "U3") (pin "14") (pinfunction "A_14") (pintype "input"))
      (node (ref "U4") (pin "14") (pinfunction "A_14") (pintype "input"))
    )
    (net (code "88") (name "/S1") (class "Default")
      (node (ref "GPIO") (pin "7") (pinfunction "7_7") (pintype "passive"))
      (node (ref "U2") (pin "2") (pinfunction "B_2") (pintype "input"))
      (node (ref "U3") (pin "2") (pinfunction "B_2") (pintype "input"))
      (node (ref "U4") (pin "2") (pinfunction "B_2") (pintype "input"))
    )
    (net (code "89") (name "/SCL") (class "Default")
      (node (ref "I2C1") (pin "2") (pinfunction "2_2") (pintype "passive"))
      (node (ref "JP2") (pin "5") (pinfunction "5_5") (pintype "passive"))
      (node (ref "U1") (pin "67") (pinfunction "SCL_67") (pintype "passive"))
    )
    (net (code "90") (name "/SDA") (class "Default")
      (node (ref "I2C1") (pin "1") (pinfunction "1_1") (pintype "passive"))
      (node (ref "JP2") (pin "4") (pinfunction "4_4") (pintype "passive"))
      (node (ref "U1") (pin "66") (pinfunction "SDA_66") (pintype "passive"))
    )
    (net (code "91") (name "/U1") (class "Default")
      (node (ref "R1") (pin "2") (pinfunction "2_2") (pintype "passive"))
      (node (ref "R2") (pin "1") (pinfunction "1_1") (pintype "passive"))
      (node (ref "U5") (pin "1") (pinfunction "ADJ_1") (pintype "input"))
    )
    (net (code "92") (name "/VSOUT{slash}A0") (class "Default")
      (node (ref "JP1") (pin "2") (pinfunction "2_2") (pintype "passive"))
      (node (ref "JP1") (pin "5") (pinfunction "5_5") (pintype "passive"))
      (node (ref "U1") (pin "22") (pinfunction "VSOUT/A0_22") (pintype "passive"))
    )
    (net (code "93") (name "/VSYNC0") (class "Default")
      (node (ref "JP1") (pin "1") (pinfunction "1_1") (pintype "passive"))
      (node (ref "U1") (pin "71") (pinfunction "VSYNC0_71") (pintype "passive"))
    )
    (net (code "94") (name "/YIN_0") (class "Default")
      (node (ref "3") (pin "1") (pinfunction "1_1") (pintype "passive"))
      (node (ref "Y0_R") (pin "2") (pinfunction "2_2") (pintype "passive"))
    )
    (net (code "95") (name "/YIN_1") (class "Default")
      (node (ref "4") (pin "1") (pinfunction "1_1") (pintype "passive"))
      (node (ref "Y1_R") (pin "2") (pinfunction "2_2") (pintype "passive"))
    )
    (net (code "96") (name "Net-(CZ-Pad2)") (class "Default")
      (node (ref "CZ") (pin "2") (pinfunction "2_2") (pintype "passive"))
      (node (ref "RZ") (pin "2") (pinfunction "2_2") (pintype "passive"))
    )
    (net (code "97") (name "unconnected-(HOOK1-Pad1)") (class "Default")
      (node (ref "HOOK1") (pin "1") (pinfunction "1_1") (pintype "passive"))
    )
    (net (code "98") (name "unconnected-(HOOK2-Pad1)") (class "Default")
      (node (ref "HOOK2") (pin "1") (pinfunction "1_1") (pintype "passive"))
    )
    (net (code "99") (name "unconnected-(I2C1-Pad3)") (class "Default")
      (node (ref "I2C1") (pin "3") (pinfunction "3_3") (pintype "passive"))
    )
    (net (code "100") (name "unconnected-(I2C1-Pad4)") (class "Default")
      (node (ref "I2C1") (pin "4") (pinfunction "4_4") (pintype "passive"))
    )
    (net (code "101") (name "unconnected-(I2C2-Pad1)") (class "Default")
      (node (ref "I2C2") (pin "1") (pinfunction "1_1") (pintype "passive"))
    )
    (net (code "102") (name "unconnected-(I2C2-Pad2)") (class "Default")
      (node (ref "I2C2") (pin "2") (pinfunction "2_2") (pintype "passive"))
    )
    (net (code "103") (name "unconnected-(I2C2-Pad3)") (class "Default")
      (node (ref "I2C2") (pin "3") (pinfunction "3_3") (pintype "passive"))
    )
    (net (code "104") (name "unconnected-(I2C2-Pad4)") (class "Default")
      (node (ref "I2C2") (pin "4") (pinfunction "4_4") (pintype "passive"))
    )
    (net (code "105") (name "unconnected-(IC2-QD-Pad3)") (class "Default")
      (node (ref "IC2") (pin "3") (pinfunction "QD_3") (pintype "tri_state"))
    )
    (net (code "106") (name "unconnected-(IC2-QG-Pad6)") (class "Default")
      (node (ref "IC2") (pin "6") (pinfunction "QG_6") (pintype "tri_state"))
    )
    (net (code "107") (name "unconnected-(IC2-SCK-Pad11)") (class "Default")
      (node (ref "IC2") (pin "11") (pinfunction "SCK_11") (pintype "input"))
    )
    (net (code "108") (name "unconnected-(IC2-SER-Pad14)") (class "Default")
      (node (ref "IC2") (pin "14") (pinfunction "SER_14") (pintype "input"))
    )
    (net (code "109") (name "unconnected-(IC3-QD-Pad3)") (class "Default")
      (node (ref "IC3") (pin "3") (pinfunction "QD_3") (pintype "tri_state"))
    )
    (net (code "110") (name "unconnected-(IC3-QG-Pad6)") (class "Default")
      (node (ref "IC3") (pin "6") (pinfunction "QG_6") (pintype "tri_state"))
    )
    (net (code "111") (name "unconnected-(IC3-SCK-Pad11)") (class "Default")
      (node (ref "IC3") (pin "11") (pinfunction "SCK_11") (pintype "input"))
    )
    (net (code "112") (name "unconnected-(IC3-SER-Pad14)") (class "Default")
      (node (ref "IC3") (pin "14") (pinfunction "SER_14") (pintype "input"))
    )
    (net (code "113") (name "unconnected-(IC4-QD-Pad3)") (class "Default")
      (node (ref "IC4") (pin "3") (pinfunction "QD_3") (pintype "tri_state"))
    )
    (net (code "114") (name "unconnected-(IC4-QG-Pad6)") (class "Default")
      (node (ref "IC4") (pin "6") (pinfunction "QG_6") (pintype "tri_state"))
    )
    (net (code "115") (name "unconnected-(IC4-SCK-Pad11)") (class "Default")
      (node (ref "IC4") (pin "11") (pinfunction "SCK_11") (pintype "input"))
    )
    (net (code "116") (name "unconnected-(IC4-SER-Pad14)") (class "Default")
      (node (ref "IC4") (pin "14") (pinfunction "SER_14") (pintype "input"))
    )
    (net (code "117") (name "unconnected-(IC5-QD-Pad3)") (class "Default")
      (node (ref "IC5") (pin "3") (pinfunction "QD_3") (pintype "tri_state"))
    )
    (net (code "118") (name "unconnected-(IC5-QG-Pad6)") (class "Default")
      (node (ref "IC5") (pin "6") (pinfunction "QG_6") (pintype "tri_state"))
    )
    (net (code "119") (name "unconnected-(IC5-SCK-Pad11)") (class "Default")
      (node (ref "IC5") (pin "11") (pinfunction "SCK_11") (pintype "input"))
    )
    (net (code "120") (name "unconnected-(IC5-SER-Pad14)") (class "Default")
      (node (ref "IC5") (pin "14") (pinfunction "SER_14") (pintype "input"))
    )
    (net (code "121") (name "unconnected-(IC6-QD-Pad3)") (class "Default")
      (node (ref "IC6") (pin "3") (pinfunction "QD_3") (pintype "tri_state"))
    )
    (net (code "122") (name "unconnected-(IC6-QG-Pad6)") (class "Default")
      (node (ref "IC6") (pin "6") (pinfunction "QG_6") (pintype "tri_state"))
    )
    (net (code "123") (name "unconnected-(IC6-SCK-Pad11)") (class "Default")
      (node (ref "IC6") (pin "11") (pinfunction "SCK_11") (pintype "input"))
    )
    (net (code "124") (name "unconnected-(IC6-SER-Pad14)") (class "Default")
      (node (ref "IC6") (pin "14") (pinfunction "SER_14") (pintype "input"))
    )
    (net (code "125") (name "unconnected-(IC7-QD-Pad3)") (class "Default")
      (node (ref "IC7") (pin "3") (pinfunction "QD_3") (pintype "tri_state"))
    )
    (net (code "126") (name "unconnected-(IC7-QG-Pad6)") (class "Default")
      (node (ref "IC7") (pin "6") (pinfunction "QG_6") (pintype "tri_state"))
    )
    (net (code "127") (name "unconnected-(IC7-SCK-Pad11)") (class "Default")
      (node (ref "IC7") (pin "11") (pinfunction "SCK_11") (pintype "input"))
    )
    (net (code "128") (name "unconnected-(IC7-SER-Pad14)") (class "Default")
      (node (ref "IC7") (pin "14") (pinfunction "SER_14") (pintype "input"))
    )
    (net (code "129") (name "unconnected-(IC8D-I0-Pad9)") (class "Default")
      (node (ref "IC8") (pin "9") (pinfunction "I0_9") (pintype "input"))
    )
    (net (code "130") (name "unconnected-(IC8D-I1-Pad8)") (class "Default")
      (node (ref "IC8") (pin "8") (pinfunction "I1_8") (pintype "input"))
    )
    (net (code "131") (name "unconnected-(IC8D-O-Pad7)") (class "Default")
      (node (ref "IC8") (pin "7") (pinfunction "O_7") (pintype "output"))
    )
    (net (code "132") (name "unconnected-(IC10A-A-Pad15)") (class "Default")
      (node (ref "IC10") (pin "15") (pinfunction "A_15") (pintype "input"))
    )
    (net (code "133") (name "unconnected-(IC10A-B-Pad1)") (class "Default")
      (node (ref "IC10") (pin "1") (pinfunction "B_1") (pintype "input"))
    )
    (net (code "134") (name "unconnected-(IC10A-BORROW-Pad13)") (class "Default")
      (node (ref "IC10") (pin "13") (pinfunction "BORROW_13") (pintype "output"))
    )
    (net (code "135") (name "unconnected-(IC10A-C-Pad10)") (class "Default")
      (node (ref "IC10") (pin "10") (pinfunction "C_10") (pintype "input"))
    )
    (net (code "136") (name "unconnected-(IC10A-CARRY-Pad12)") (class "Default")
      (node (ref "IC10") (pin "12") (pinfunction "CARRY_12") (pintype "output"))
    )
    (net (code "137") (name "unconnected-(IC10A-D-Pad9)") (class "Default")
      (node (ref "IC10") (pin "9") (pinfunction "D_9") (pintype "input"))
    )
    (net (code "138") (name "unconnected-(SPI0-Pad1)") (class "Default")
      (node (ref "SPI0") (pin "1") (pinfunction "1_1") (pintype "passive"))
    )
    (net (code "139") (name "unconnected-(SPI0-Pad2)") (class "Default")
      (node (ref "SPI0") (pin "2") (pinfunction "2_2") (pintype "passive"))
    )
    (net (code "140") (name "unconnected-(SPI0-Pad3)") (class "Default")
      (node (ref "SPI0") (pin "3") (pinfunction "3_3") (pintype "passive"))
    )
    (net (code "141") (name "unconnected-(SPI0-Pad4)") (class "Default")
      (node (ref "SPI0") (pin "4") (pinfunction "4_4") (pintype "passive"))
    )
    (net (code "142") (name "unconnected-(SPI0-Pad5)") (class "Default")
      (node (ref "SPI0") (pin "5") (pinfunction "5_5") (pintype "passive"))
    )
    (net (code "143") (name "unconnected-(SPI0-Pad6)") (class "Default")
      (node (ref "SPI0") (pin "6") (pinfunction "6_6") (pintype "passive"))
    )
    (net (code "144") (name "unconnected-(SPI1-Pad1)") (class "Default")
      (node (ref "SPI1") (pin "1") (pinfunction "1_1") (pintype "passive"))
    )
    (net (code "145") (name "unconnected-(SPI1-Pad2)") (class "Default")
      (node (ref "SPI1") (pin "2") (pinfunction "2_2") (pintype "passive"))
    )
    (net (code "146") (name "unconnected-(SPI1-Pad3)") (class "Default")
      (node (ref "SPI1") (pin "3") (pinfunction "3_3") (pintype "passive"))
    )
    (net (code "147") (name "unconnected-(SPI1-Pad4)") (class "Default")
      (node (ref "SPI1") (pin "4") (pinfunction "4_4") (pintype "passive"))
    )
    (net (code "148") (name "unconnected-(SPI1-Pad5)") (class "Default")
      (node (ref "SPI1") (pin "5") (pinfunction "5_5") (pintype "passive"))
    )
    (net (code "149") (name "unconnected-(SPI1-Pad6)") (class "Default")
      (node (ref "SPI1") (pin "6") (pinfunction "6_6") (pintype "passive"))
    )
    (net (code "150") (name "unconnected-(U1-NC-Pad63)") (class "Default")
      (node (ref "U1") (pin "63") (pinfunction "NC_63") (pintype "passive"))
    )
    (net (code "151") (name "unconnected-(U1-NC_2-Pad50)") (class "Default")
      (node (ref "U1") (pin "50") (pinfunction "NC_2_50") (pintype "passive"))
    )
    (net (code "152") (name "unconnected-(U1-NC_3-Pad51)") (class "Default")
      (node (ref "U1") (pin "51") (pinfunction "NC_3_51") (pintype "passive"))
    )
    (net (code "153") (name "unconnected-(U1-NC_4-Pad36)") (class "Default")
      (node (ref "U1") (pin "36") (pinfunction "NC_4_36") (pintype "passive"))
    )
    (net (code "154") (name "unconnected-(U1-NC_5-Pad62)") (class "Default")
      (node (ref "U1") (pin "62") (pinfunction "NC_5_62") (pintype "passive"))
    )
    (net (code "155") (name "unconnected-(U1-NC_6-Pad37)") (class "Default")
      (node (ref "U1") (pin "37") (pinfunction "NC_6_37") (pintype "passive"))
    )
    (net (code "156") (name "unconnected-(U1-REFCM-Pad19)") (class "Default")
      (node (ref "U1") (pin "19") (pinfunction "REFCM_19") (pintype "passive"))
    )
    (net (code "157") (name "unconnected-(U1-SOGIN0-Pad8)") (class "Default")
      (node (ref "U1") (pin "8") (pinfunction "SOGIN0_8") (pintype "passive"))
    )
    (net (code "158") (name "unconnected-(U1-SOGIN1-Pad12)") (class "Default")
      (node (ref "U1") (pin "12") (pinfunction "SOGIN1_12") (pintype "passive"))
    )
    (net (code "159") (name "unconnected-(U1-SOGOUT-Pad24)") (class "Default")
      (node (ref "U1") (pin "24") (pinfunction "SOGOUT_24") (pintype "passive"))
    )
    (net (code "160") (name "unconnected-(UART-Pad1)") (class "Default")
      (node (ref "UART") (pin "1") (pinfunction "1_1") (pintype "passive"))
    )
    (net (code "161") (name "unconnected-(UART-Pad2)") (class "Default")
      (node (ref "UART") (pin "2") (pinfunction "2_2") (pintype "passive"))
    )
    (net (code "162") (name "unconnected-(UART-Pad3)") (class "Default")
      (node (ref "UART") (pin "3") (pinfunction "3_3") (pintype "passive"))
    )
    (net (code "163") (name "unconnected-(UART-Pad4)") (class "Default")
      (node (ref "UART") (pin "4") (pinfunction "4_4") (pintype "passive"))
    )
  )
)
